# BaseBoard_1.net
KiCad netlist of a schematic drawn in EAGLE
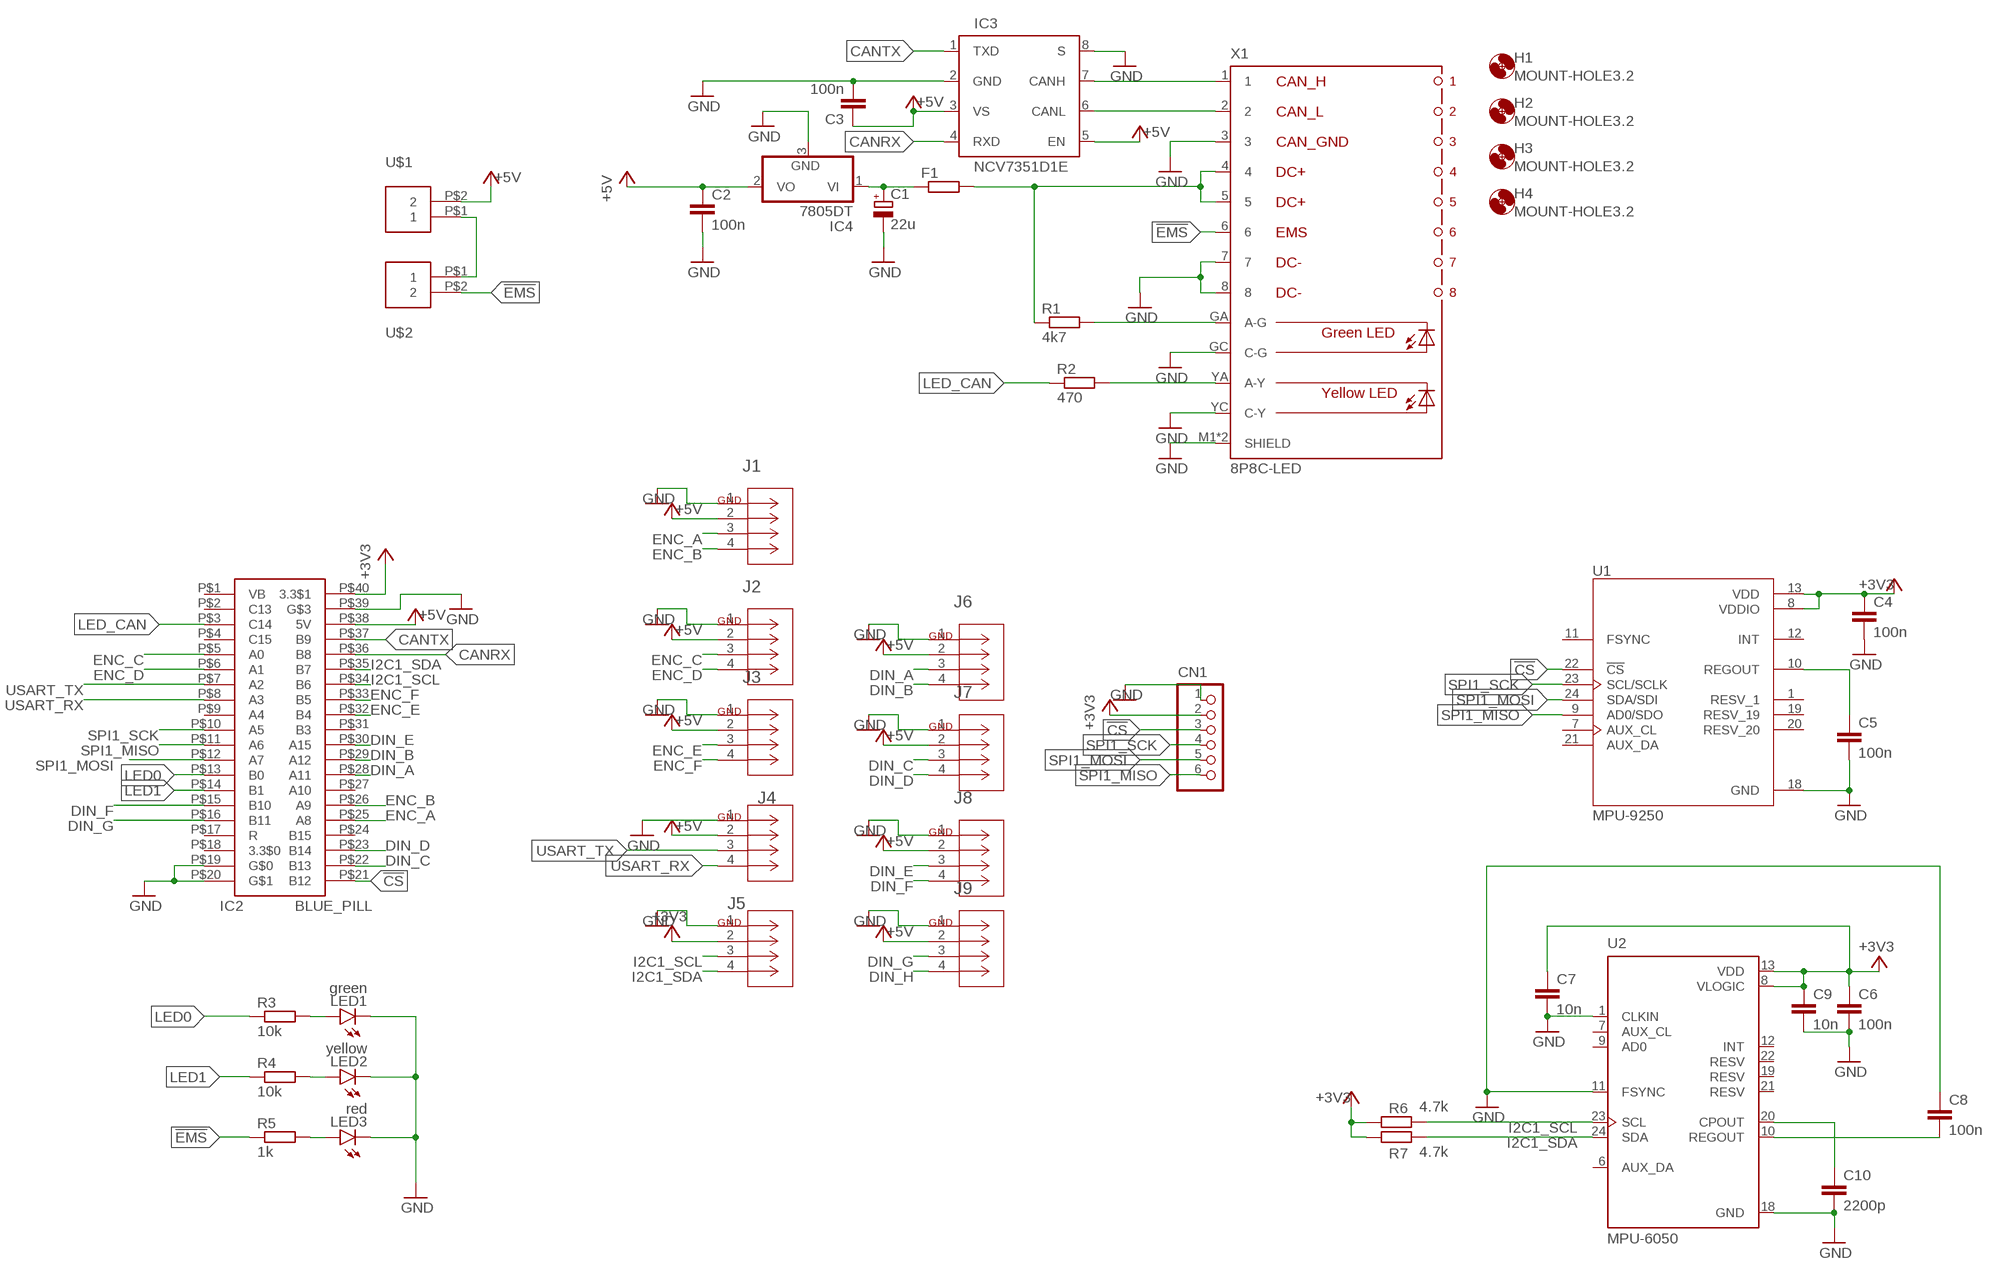
[diagram p0: schematic, sheet 1]

(export (version "E")
  (design (tool "Eeschema 10.0.6"))
  (components
    (comp (ref "C1")
      (value "22u")
      (footprint "eagle-import:E2,5-5")
      (libsource (lib "eagle-import") (part "CPOL-EUE2.5-5"))
    )
    (comp (ref "C2")
      (value "100n")
      (footprint "eagle-import:C0603")
      (libsource (lib "eagle-import") (part "C-EUC0603"))
    )
    (comp (ref "C3")
      (value "100n")
      (footprint "eagle-import:C0603")
      (libsource (lib "eagle-import") (part "C-EUC0603"))
    )
    (comp (ref "C4")
      (value "100n")
      (footprint "eagle-import:C0603")
      (libsource (lib "eagle-import") (part "C-EUC0603"))
    )
    (comp (ref "C5")
      (value "100n")
      (footprint "eagle-import:C0603")
      (libsource (lib "eagle-import") (part "C-EUC0603"))
    )
    (comp (ref "C6")
      (value "100n")
      (footprint "eagle-import:C0603")
      (libsource (lib "eagle-import") (part "C-EUC0603"))
    )
    (comp (ref "C7")
      (value "10n")
      (footprint "eagle-import:C0603")
      (libsource (lib "eagle-import") (part "C-EUC0603"))
    )
    (comp (ref "C8")
      (value "100n")
      (footprint "eagle-import:C0603")
      (libsource (lib "eagle-import") (part "C-EUC0603"))
    )
    (comp (ref "C9")
      (value "10n")
      (footprint "eagle-import:C0603")
      (libsource (lib "eagle-import") (part "C-EUC0603"))
    )
    (comp (ref "C10")
      (value "2200p")
      (footprint "eagle-import:C0603")
      (libsource (lib "eagle-import") (part "C-EUC0603"))
    )
    (comp (ref "CN1")
      (value "S6B-XH-A")
      (footprint "eagle-import:S6B-XH-A")
      (libsource (lib "eagle-import") (part "S6B-XH-A"))
    )
    (comp (ref "F1")
      (value "R-EU_R1206")
      (footprint "eagle-import:R1206")
      (libsource (lib "eagle-import") (part "R-EU_R1206"))
    )
    (comp (ref "H1")
      (value "MOUNT-HOLE3.2")
      (footprint "eagle-import:3,2")
      (libsource (lib "eagle-import") (part "MOUNT-HOLE3.2"))
    )
    (comp (ref "H2")
      (value "MOUNT-HOLE3.2")
      (footprint "eagle-import:3,2")
      (libsource (lib "eagle-import") (part "MOUNT-HOLE3.2"))
    )
    (comp (ref "H3")
      (value "MOUNT-HOLE3.2")
      (footprint "eagle-import:3,2")
      (libsource (lib "eagle-import") (part "MOUNT-HOLE3.2"))
    )
    (comp (ref "H4")
      (value "MOUNT-HOLE3.2")
      (footprint "eagle-import:3,2")
      (libsource (lib "eagle-import") (part "MOUNT-HOLE3.2"))
    )
    (comp (ref "IC2")
      (value "BLUE_PILL")
      (footprint "eagle-import:BLUE_PILL")
      (libsource (lib "eagle-import") (part "BLUE_PILL"))
    )
    (comp (ref "IC3")
      (value "NCV7351D1E")
      (footprint "eagle-import:SO08")
      (libsource (lib "eagle-import") (part "NCV7351D1E"))
    )
    (comp (ref "IC4")
      (value "7805DT")
      (footprint "eagle-import:TO252")
      (libsource (lib "eagle-import") (part "78DT05"))
    )
    (comp (ref "J1")
      (value "EP2.5-4-SIDE")
      (footprint "eagle-import:CONN4_1744426-4")
      (fields (field (name "MANUFACTURER_PART_NUMBER") "17444264"))
      (libsource (lib "eagle-import") (part "EP2.5-4-SIDE"))
    )
    (comp (ref "J2")
      (value "EP2.5-4-SIDE")
      (footprint "eagle-import:CONN4_1744426-4")
      (fields (field (name "MANUFACTURER_PART_NUMBER") "17444264"))
      (libsource (lib "eagle-import") (part "EP2.5-4-SIDE"))
    )
    (comp (ref "J3")
      (value "EP2.5-4-SIDE")
      (footprint "eagle-import:CONN4_1744426-4")
      (fields (field (name "MANUFACTURER_PART_NUMBER") "17444264"))
      (libsource (lib "eagle-import") (part "EP2.5-4-SIDE"))
    )
    (comp (ref "J4")
      (value "EP2.5-4-SIDE")
      (footprint "eagle-import:CONN4_1744426-4")
      (fields (field (name "MANUFACTURER_PART_NUMBER") "17444264"))
      (libsource (lib "eagle-import") (part "EP2.5-4-SIDE"))
    )
    (comp (ref "J5")
      (value "EP2.5-4-SIDE")
      (footprint "eagle-import:CONN4_1744426-4")
      (fields (field (name "MANUFACTURER_PART_NUMBER") "17444264"))
      (libsource (lib "eagle-import") (part "EP2.5-4-SIDE"))
    )
    (comp (ref "J6")
      (value "EP2.5-4-SIDE")
      (footprint "eagle-import:CONN4_1744426-4")
      (fields (field (name "MANUFACTURER_PART_NUMBER") "17444264"))
      (libsource (lib "eagle-import") (part "EP2.5-4-SIDE"))
    )
    (comp (ref "J7")
      (value "EP2.5-4-SIDE")
      (footprint "eagle-import:CONN4_1744426-4")
      (fields (field (name "MANUFACTURER_PART_NUMBER") "17444264"))
      (libsource (lib "eagle-import") (part "EP2.5-4-SIDE"))
    )
    (comp (ref "J8")
      (value "EP2.5-4-SIDE")
      (footprint "eagle-import:CONN4_1744426-4")
      (fields (field (name "MANUFACTURER_PART_NUMBER") "17444264"))
      (libsource (lib "eagle-import") (part "EP2.5-4-SIDE"))
    )
    (comp (ref "J9")
      (value "EP2.5-4-SIDE")
      (footprint "eagle-import:CONN4_1744426-4")
      (fields (field (name "MANUFACTURER_PART_NUMBER") "17444264"))
      (libsource (lib "eagle-import") (part "EP2.5-4-SIDE"))
    )
    (comp (ref "LED1")
      (value "green")
      (footprint "eagle-import:CHIPLED_0805")
      (libsource (lib "eagle-import") (part "LEDCHIPLED_0805"))
    )
    (comp (ref "LED2")
      (value "yellow")
      (footprint "eagle-import:CHIPLED_0805")
      (libsource (lib "eagle-import") (part "LEDCHIPLED_0805"))
    )
    (comp (ref "LED3")
      (value "red")
      (footprint "eagle-import:CHIPLED_0805")
      (libsource (lib "eagle-import") (part "LEDCHIPLED_0805"))
    )
    (comp (ref "R1")
      (value "4k7")
      (footprint "eagle-import:R0603")
      (libsource (lib "eagle-import") (part "R-EU_R0603"))
    )
    (comp (ref "R2")
      (value "470")
      (footprint "eagle-import:R0603")
      (libsource (lib "eagle-import") (part "R-EU_R0603"))
    )
    (comp (ref "R3")
      (value "10k")
      (footprint "eagle-import:R0603")
      (libsource (lib "eagle-import") (part "R-EU_R0603"))
    )
    (comp (ref "R4")
      (value "10k")
      (footprint "eagle-import:R0603")
      (libsource (lib "eagle-import") (part "R-EU_R0603"))
    )
    (comp (ref "R5")
      (value "1k")
      (footprint "eagle-import:R0603")
      (libsource (lib "eagle-import") (part "R-EU_R0603"))
    )
    (comp (ref "R6")
      (value "4.7k")
      (footprint "eagle-import:R0603")
      (libsource (lib "eagle-import") (part "R-EU_R0603"))
    )
    (comp (ref "R7")
      (value "4.7k")
      (footprint "eagle-import:R0603")
      (libsource (lib "eagle-import") (part "R-EU_R0603"))
    )
    (comp (ref "U$1")
      (value "XH-2-STRAIGHT")
      (footprint "eagle-import:CON-XH-2-STRAIGHT")
      (libsource (lib "eagle-import") (part "XH-2-STRAIGHT"))
    )
    (comp (ref "U$2")
      (value "XH-2-STRAIGHT")
      (footprint "eagle-import:CON-XH-2-STRAIGHT")
      (libsource (lib "eagle-import") (part "XH-2-STRAIGHT"))
    )
    (comp (ref "U1")
      (value "MPU-9250")
      (footprint "eagle-import:QFN40P300X300X105-24N")
      (fields (field (name "MF") "TDK InvenSense"))
      (libsource (lib "eagle-import") (part "MPU-9250"))
    )
    (comp (ref "U2")
      (value "MPU-6050")
      (footprint "eagle-import:QFN50P400X400X95-24N")
      (fields (field (name "MF") "TDK InvenSense"))
      (libsource (lib "eagle-import") (part "MPU-6050"))
    )
    (comp (ref "X1")
      (value "8P8C-LED")
      (footprint "eagle-import:8P8C-LED")
      (libsource (lib "eagle-import") (part "8P8C-LED"))
    )
  )
  (nets
    (net (code "1") (name "+3V3") (class "Default")
      (node (ref "C4") (pin "1") (pinfunction "1_1") (pintype "passive"))
      (node (ref "C6") (pin "1") (pinfunction "1_1") (pintype "passive"))
      (node (ref "C7") (pin "1") (pinfunction "1_1") (pintype "passive"))
      (node (ref "C9") (pin "1") (pinfunction "1_1") (pintype "passive"))
      (node (ref "CN1") (pin "2") (pinfunction "2_2") (pintype "passive"))
      (node (ref "IC2") (pin "P$40") (pinfunction "3.3$1_P$40") (pintype "passive"))
      (node (ref "J5") (pin "2") (pinfunction "2_2") (pintype "passive"))
      (node (ref "R6") (pin "1") (pinfunction "1_1") (pintype "passive"))
      (node (ref "R7") (pin "1") (pinfunction "1_1") (pintype "passive"))
      (node (ref "U1") (pin "13") (pinfunction "VDD_13") (pintype "power_in"))
      (node (ref "U1") (pin "8") (pinfunction "VDDIO_8") (pintype "power_in"))
      (node (ref "U2") (pin "13") (pinfunction "VDD_13") (pintype "power_in"))
      (node (ref "U2") (pin "8") (pinfunction "VLOGIC_8") (pintype "power_in"))
    )
    (net (code "2") (name "+5V") (class "Default")
      (node (ref "C2") (pin "1") (pinfunction "1_1") (pintype "passive"))
      (node (ref "C3") (pin "1") (pinfunction "1_1") (pintype "passive"))
      (node (ref "IC2") (pin "P$38") (pinfunction "5V_P$38") (pintype "bidirectional"))
      (node (ref "IC3") (pin "3") (pinfunction "VS_3") (pintype "power_in"))
      (node (ref "IC3") (pin "5") (pinfunction "EN_5") (pintype "input"))
      (node (ref "IC4") (pin "2") (pinfunction "VO_2") (pintype "passive"))
      (node (ref "J1") (pin "2") (pinfunction "2_2") (pintype "passive"))
      (node (ref "J2") (pin "2") (pinfunction "2_2") (pintype "passive"))
      (node (ref "J3") (pin "2") (pinfunction "2_2") (pintype "passive"))
      (node (ref "J4") (pin "2") (pinfunction "2_2") (pintype "passive"))
      (node (ref "J6") (pin "2") (pinfunction "2_2") (pintype "passive"))
      (node (ref "J7") (pin "2") (pinfunction "2_2") (pintype "passive"))
      (node (ref "J8") (pin "2") (pinfunction "2_2") (pintype "passive"))
      (node (ref "J9") (pin "2") (pinfunction "2_2") (pintype "passive"))
      (node (ref "U$1") (pin "P$2") (pinfunction "2_P$2") (pintype "bidirectional"))
    )
    (net (code "3") (name "/DIN_A") (class "Default")
      (node (ref "IC2") (pin "P$28") (pinfunction "A11_P$28") (pintype "bidirectional"))
      (node (ref "J6") (pin "3") (pinfunction "3_3") (pintype "passive"))
    )
    (net (code "4") (name "/DIN_B") (class "Default")
      (node (ref "IC2") (pin "P$29") (pinfunction "A12_P$29") (pintype "bidirectional"))
      (node (ref "J6") (pin "4") (pinfunction "4_4") (pintype "passive"))
    )
    (net (code "5") (name "/DIN_C") (class "Default")
      (node (ref "IC2") (pin "P$22") (pinfunction "B13_P$22") (pintype "bidirectional"))
      (node (ref "J7") (pin "3") (pinfunction "3_3") (pintype "passive"))
    )
    (net (code "6") (name "/DIN_D") (class "Default")
      (node (ref "IC2") (pin "P$23") (pinfunction "B14_P$23") (pintype "bidirectional"))
      (node (ref "J7") (pin "4") (pinfunction "4_4") (pintype "passive"))
    )
    (net (code "7") (name "/DIN_E") (class "Default")
      (node (ref "IC2") (pin "P$30") (pinfunction "A15_P$30") (pintype "bidirectional"))
      (node (ref "J8") (pin "3") (pinfunction "3_3") (pintype "passive"))
    )
    (net (code "8") (name "/DIN_F") (class "Default")
      (node (ref "IC2") (pin "P$15") (pinfunction "B10_P$15") (pintype "bidirectional"))
      (node (ref "J8") (pin "4") (pinfunction "4_4") (pintype "passive"))
    )
    (net (code "9") (name "/DIN_G") (class "Default")
      (node (ref "IC2") (pin "P$16") (pinfunction "B11_P$16") (pintype "bidirectional"))
      (node (ref "J9") (pin "3") (pinfunction "3_3") (pintype "passive"))
    )
    (net (code "10") (name "/DIN_H") (class "Default")
      (node (ref "J9") (pin "4") (pinfunction "4_4") (pintype "passive"))
    )
    (net (code "11") (name "/ENC_A") (class "Default")
      (node (ref "IC2") (pin "P$25") (pinfunction "A8_P$25") (pintype "bidirectional"))
      (node (ref "J1") (pin "3") (pinfunction "3_3") (pintype "passive"))
    )
    (net (code "12") (name "/ENC_B") (class "Default")
      (node (ref "IC2") (pin "P$26") (pinfunction "A9_P$26") (pintype "bidirectional"))
      (node (ref "J1") (pin "4") (pinfunction "4_4") (pintype "passive"))
    )
    (net (code "13") (name "/ENC_C") (class "Default")
      (node (ref "IC2") (pin "P$5") (pinfunction "A0_P$5") (pintype "bidirectional"))
      (node (ref "J2") (pin "3") (pinfunction "3_3") (pintype "passive"))
    )
    (net (code "14") (name "/ENC_D") (class "Default")
      (node (ref "IC2") (pin "P$6") (pinfunction "A1_P$6") (pintype "bidirectional"))
      (node (ref "J2") (pin "4") (pinfunction "4_4") (pintype "passive"))
    )
    (net (code "15") (name "/ENC_E") (class "Default")
      (node (ref "IC2") (pin "P$32") (pinfunction "B4_P$32") (pintype "bidirectional"))
      (node (ref "J3") (pin "3") (pinfunction "3_3") (pintype "passive"))
    )
    (net (code "16") (name "/ENC_F") (class "Default")
      (node (ref "IC2") (pin "P$33") (pinfunction "B5_P$33") (pintype "bidirectional"))
      (node (ref "J3") (pin "4") (pinfunction "4_4") (pintype "passive"))
    )
    (net (code "17") (name "/I2C1_SCL") (class "Default")
      (node (ref "IC2") (pin "P$34") (pinfunction "B6_P$34") (pintype "bidirectional"))
      (node (ref "J5") (pin "3") (pinfunction "3_3") (pintype "passive"))
      (node (ref "R6") (pin "2") (pinfunction "2_2") (pintype "passive"))
      (node (ref "U2") (pin "23") (pinfunction "SCL_23") (pintype "input"))
    )
    (net (code "18") (name "/I2C1_SDA") (class "Default")
      (node (ref "IC2") (pin "P$35") (pinfunction "B7_P$35") (pintype "bidirectional"))
      (node (ref "J5") (pin "4") (pinfunction "4_4") (pintype "passive"))
      (node (ref "R7") (pin "2") (pinfunction "2_2") (pintype "passive"))
      (node (ref "U2") (pin "24") (pinfunction "SDA_24") (pintype "bidirectional"))
    )
    (net (code "19") (name "/~{CS}") (class "Default")
      (node (ref "CN1") (pin "3") (pinfunction "3_3") (pintype "passive"))
      (node (ref "IC2") (pin "P$21") (pinfunction "B12_P$21") (pintype "bidirectional"))
      (node (ref "U1") (pin "22") (pinfunction "~{CS}_22") (pintype "input"))
    )
    (net (code "20") (name "/~{EMS}") (class "Default")
      (node (ref "R5") (pin "1") (pinfunction "1_1") (pintype "passive"))
      (node (ref "U$2") (pin "P$2") (pinfunction "2_P$2") (pintype "bidirectional"))
      (node (ref "X1") (pin "6") (pinfunction "6_6") (pintype "input"))
    )
    (net (code "21") (name "CANRX") (class "Default")
      (node (ref "IC2") (pin "P$36") (pinfunction "B8_P$36") (pintype "bidirectional"))
      (node (ref "IC3") (pin "4") (pinfunction "RXD_4") (pintype "output"))
    )
    (net (code "22") (name "CANTX") (class "Default")
      (node (ref "IC2") (pin "P$37") (pinfunction "B9_P$37") (pintype "bidirectional"))
      (node (ref "IC3") (pin "1") (pinfunction "TXD_1") (pintype "input"))
    )
    (net (code "23") (name "GND") (class "Default")
      (node (ref "C1") (pin "-") (pinfunction "-_-") (pintype "passive"))
      (node (ref "C10") (pin "2") (pinfunction "2_2") (pintype "passive"))
      (node (ref "C2") (pin "2") (pinfunction "2_2") (pintype "passive"))
      (node (ref "C3") (pin "2") (pinfunction "2_2") (pintype "passive"))
      (node (ref "C4") (pin "2") (pinfunction "2_2") (pintype "passive"))
      (node (ref "C5") (pin "2") (pinfunction "2_2") (pintype "passive"))
      (node (ref "C6") (pin "2") (pinfunction "2_2") (pintype "passive"))
      (node (ref "C7") (pin "2") (pinfunction "2_2") (pintype "passive"))
      (node (ref "C8") (pin "1") (pinfunction "1_1") (pintype "passive"))
      (node (ref "C9") (pin "2") (pinfunction "2_2") (pintype "passive"))
      (node (ref "CN1") (pin "1") (pinfunction "1_1") (pintype "passive"))
      (node (ref "IC2") (pin "P$19") (pinfunction "G$0_P$19") (pintype "passive"))
      (node (ref "IC2") (pin "P$20") (pinfunction "G$1_P$20") (pintype "passive"))
      (node (ref "IC2") (pin "P$39") (pinfunction "G$3_P$39") (pintype "passive"))
      (node (ref "IC3") (pin "2") (pinfunction "GND_2") (pintype "power_in"))
      (node (ref "IC3") (pin "8") (pinfunction "S_8") (pintype "input"))
      (node (ref "IC4") (pin "3") (pinfunction "GND_3") (pintype "passive"))
      (node (ref "J1") (pin "1") (pinfunction "1_1") (pintype "passive"))
      (node (ref "J2") (pin "1") (pinfunction "1_1") (pintype "passive"))
      (node (ref "J3") (pin "1") (pinfunction "1_1") (pintype "passive"))
      (node (ref "J4") (pin "1") (pinfunction "1_1") (pintype "passive"))
      (node (ref "J5") (pin "1") (pinfunction "1_1") (pintype "passive"))
      (node (ref "J6") (pin "1") (pinfunction "1_1") (pintype "passive"))
      (node (ref "J7") (pin "1") (pinfunction "1_1") (pintype "passive"))
      (node (ref "J8") (pin "1") (pinfunction "1_1") (pintype "passive"))
      (node (ref "J9") (pin "1") (pinfunction "1_1") (pintype "passive"))
      (node (ref "LED1") (pin "C") (pinfunction "C_C") (pintype "passive"))
      (node (ref "LED2") (pin "C") (pinfunction "C_C") (pintype "passive"))
      (node (ref "LED3") (pin "C") (pinfunction "C_C") (pintype "passive"))
      (node (ref "U1") (pin "18") (pinfunction "GND_18") (pintype "power_in"))
      (node (ref "U2") (pin "1") (pinfunction "CLKIN_1") (pintype "input"))
      (node (ref "U2") (pin "11") (pinfunction "FSYNC_11") (pintype "input"))
      (node (ref "U2") (pin "18") (pinfunction "GND_18") (pintype "power_in"))
      (node (ref "X1") (pin "3") (pinfunction "3_3") (pintype "input"))
      (node (ref "X1") (pin "7") (pinfunction "7_7") (pintype "input"))
      (node (ref "X1") (pin "8") (pinfunction "8_8") (pintype "input"))
      (node (ref "X1") (pin "GC") (pinfunction "C-G_GC") (pintype "passive"))
      (node (ref "X1") (pin "M1") (pinfunction "SHIELD_M1") (pintype "passive"))
      (node (ref "X1") (pin "M2") (pinfunction "SHIELD_M2") (pintype "passive"))
      (node (ref "X1") (pin "YC") (pinfunction "C-Y_YC") (pintype "passive"))
    )
    (net (code "24") (name "LED0") (class "Default")
      (node (ref "IC2") (pin "P$13") (pinfunction "B0_P$13") (pintype "bidirectional"))
      (node (ref "R3") (pin "1") (pinfunction "1_1") (pintype "passive"))
    )
    (net (code "25") (name "LED1") (class "Default")
      (node (ref "IC2") (pin "P$14") (pinfunction "B1_P$14") (pintype "bidirectional"))
      (node (ref "R4") (pin "1") (pinfunction "1_1") (pintype "passive"))
    )
    (net (code "26") (name "LED_CAN") (class "Default")
      (node (ref "IC2") (pin "P$3") (pinfunction "C14_P$3") (pintype "bidirectional"))
      (node (ref "R2") (pin "1") (pinfunction "1_1") (pintype "passive"))
    )
    (net (code "27") (name "Net-(F1-Pad2)") (class "Default")
      (node (ref "F1") (pin "2") (pinfunction "2_2") (pintype "passive"))
      (node (ref "R1") (pin "1") (pinfunction "1_1") (pintype "passive"))
      (node (ref "X1") (pin "4") (pinfunction "4_4") (pintype "input"))
      (node (ref "X1") (pin "5") (pinfunction "5_5") (pintype "input"))
    )
    (net (code "28") (name "Net-(IC3-CANH)") (class "Default")
      (node (ref "IC3") (pin "7") (pinfunction "CANH_7") (pintype "output"))
      (node (ref "X1") (pin "1") (pinfunction "1_1") (pintype "input"))
    )
    (net (code "29") (name "Net-(IC3-CANL)") (class "Default")
      (node (ref "IC3") (pin "6") (pinfunction "CANL_6") (pintype "output"))
      (node (ref "X1") (pin "2") (pinfunction "2_2") (pintype "input"))
    )
    (net (code "30") (name "Net-(IC4-VI)") (class "Default")
      (node (ref "C1") (pin "+") (pinfunction "+_+") (pintype "passive"))
      (node (ref "F1") (pin "1") (pinfunction "1_1") (pintype "passive"))
      (node (ref "IC4") (pin "1") (pinfunction "VI_1") (pintype "input"))
    )
    (net (code "31") (name "Net-(LED1-PadA)") (class "Default")
      (node (ref "LED1") (pin "A") (pinfunction "A_A") (pintype "passive"))
      (node (ref "R3") (pin "2") (pinfunction "2_2") (pintype "passive"))
    )
    (net (code "32") (name "Net-(LED2-PadA)") (class "Default")
      (node (ref "LED2") (pin "A") (pinfunction "A_A") (pintype "passive"))
      (node (ref "R4") (pin "2") (pinfunction "2_2") (pintype "passive"))
    )
    (net (code "33") (name "Net-(LED3-PadA)") (class "Default")
      (node (ref "LED3") (pin "A") (pinfunction "A_A") (pintype "passive"))
      (node (ref "R5") (pin "2") (pinfunction "2_2") (pintype "passive"))
    )
    (net (code "34") (name "Net-(U$1-1)") (class "Default")
      (node (ref "U$1") (pin "P$1") (pinfunction "1_P$1") (pintype "bidirectional"))
      (node (ref "U$2") (pin "P$1") (pinfunction "1_P$1") (pintype "bidirectional"))
    )
    (net (code "35") (name "Net-(U1-REGOUT)") (class "Default")
      (node (ref "C5") (pin "1") (pinfunction "1_1") (pintype "passive"))
      (node (ref "U1") (pin "10") (pinfunction "REGOUT_10") (pintype "output"))
    )
    (net (code "36") (name "Net-(U2-CPOUT)") (class "Default")
      (node (ref "C10") (pin "1") (pinfunction "1_1") (pintype "passive"))
      (node (ref "U2") (pin "20") (pinfunction "CPOUT_20") (pintype "passive"))
    )
    (net (code "37") (name "Net-(U2-REGOUT)") (class "Default")
      (node (ref "C8") (pin "2") (pinfunction "2_2") (pintype "passive"))
      (node (ref "U2") (pin "10") (pinfunction "REGOUT_10") (pintype "passive"))
    )
    (net (code "38") (name "Net-(X1-A-G)") (class "Default")
      (node (ref "R1") (pin "2") (pinfunction "2_2") (pintype "passive"))
      (node (ref "X1") (pin "GA") (pinfunction "A-G_GA") (pintype "passive"))
    )
    (net (code "39") (name "Net-(X1-A-Y)") (class "Default")
      (node (ref "R2") (pin "2") (pinfunction "2_2") (pintype "passive"))
      (node (ref "X1") (pin "YA") (pinfunction "A-Y_YA") (pintype "passive"))
    )
    (net (code "40") (name "SPI1_MISO") (class "Default")
      (node (ref "CN1") (pin "6") (pinfunction "6_6") (pintype "passive"))
      (node (ref "IC2") (pin "P$11") (pinfunction "A6_P$11") (pintype "bidirectional"))
      (node (ref "U1") (pin "9") (pinfunction "AD0/SDO_9") (pintype "output"))
    )
    (net (code "41") (name "SPI1_MOSI") (class "Default")
      (node (ref "CN1") (pin "5") (pinfunction "5_5") (pintype "passive"))
      (node (ref "IC2") (pin "P$12") (pinfunction "A7_P$12") (pintype "bidirectional"))
      (node (ref "U1") (pin "24") (pinfunction "SDA/SDI_24") (pintype "bidirectional"))
    )
    (net (code "42") (name "SPI1_SCK") (class "Default")
      (node (ref "CN1") (pin "4") (pinfunction "4_4") (pintype "passive"))
      (node (ref "IC2") (pin "P$10") (pinfunction "A5_P$10") (pintype "bidirectional"))
      (node (ref "U1") (pin "23") (pinfunction "SCL/SCLK_23") (pintype "input"))
    )
    (net (code "43") (name "USART_RX") (class "Default")
      (node (ref "IC2") (pin "P$8") (pinfunction "A3_P$8") (pintype "bidirectional"))
      (node (ref "J4") (pin "4") (pinfunction "4_4") (pintype "passive"))
    )
    (net (code "44") (name "USART_TX") (class "Default")
      (node (ref "IC2") (pin "P$7") (pinfunction "A2_P$7") (pintype "bidirectional"))
      (node (ref "J4") (pin "3") (pinfunction "3_3") (pintype "passive"))
    )
    (net (code "45") (name "unconnected-(IC2-3.3$0-PadP$18)") (class "Default")
      (node (ref "IC2") (pin "P$18") (pinfunction "3.3$0_P$18") (pintype "passive"))
    )
    (net (code "46") (name "unconnected-(IC2-A4-PadP$9)") (class "Default")
      (node (ref "IC2") (pin "P$9") (pinfunction "A4_P$9") (pintype "bidirectional"))
    )
    (net (code "47") (name "unconnected-(IC2-A10-PadP$27)") (class "Default")
      (node (ref "IC2") (pin "P$27") (pinfunction "A10_P$27") (pintype "bidirectional"))
    )
    (net (code "48") (name "unconnected-(IC2-B3-PadP$31)") (class "Default")
      (node (ref "IC2") (pin "P$31") (pinfunction "B3_P$31") (pintype "bidirectional"))
    )
    (net (code "49") (name "unconnected-(IC2-B15-PadP$24)") (class "Default")
      (node (ref "IC2") (pin "P$24") (pinfunction "B15_P$24") (pintype "bidirectional"))
    )
    (net (code "50") (name "unconnected-(IC2-C13-PadP$2)") (class "Default")
      (node (ref "IC2") (pin "P$2") (pinfunction "C13_P$2") (pintype "bidirectional"))
    )
    (net (code "51") (name "unconnected-(IC2-C15-PadP$4)") (class "Default")
      (node (ref "IC2") (pin "P$4") (pinfunction "C15_P$4") (pintype "bidirectional"))
    )
    (net (code "52") (name "unconnected-(IC2-R-PadP$17)") (class "Default")
      (node (ref "IC2") (pin "P$17") (pinfunction "R_P$17") (pintype "bidirectional"))
    )
    (net (code "53") (name "unconnected-(IC2-VB-PadP$1)") (class "Default")
      (node (ref "IC2") (pin "P$1") (pinfunction "VB_P$1") (pintype "bidirectional"))
    )
    (net (code "54") (name "unconnected-(U1-AUX_CL-Pad7)") (class "Default")
      (node (ref "U1") (pin "7") (pinfunction "AUX_CL_7") (pintype "input"))
    )
    (net (code "55") (name "unconnected-(U1-AUX_DA-Pad21)") (class "Default")
      (node (ref "U1") (pin "21") (pinfunction "AUX_DA_21") (pintype "input"))
    )
    (net (code "56") (name "unconnected-(U1-FSYNC-Pad11)") (class "Default")
      (node (ref "U1") (pin "11") (pinfunction "FSYNC_11") (pintype "input"))
    )
    (net (code "57") (name "unconnected-(U1-INT-Pad12)") (class "Default")
      (node (ref "U1") (pin "12") (pinfunction "INT_12") (pintype "output"))
    )
    (net (code "58") (name "unconnected-(U1-RESV_1-Pad1)") (class "Default")
      (node (ref "U1") (pin "1") (pinfunction "RESV_1_1") (pintype "passive"))
    )
    (net (code "59") (name "unconnected-(U1-RESV_19-Pad19)") (class "Default")
      (node (ref "U1") (pin "19") (pinfunction "RESV_19_19") (pintype "passive"))
    )
    (net (code "60") (name "unconnected-(U1-RESV_20-Pad20)") (class "Default")
      (node (ref "U1") (pin "20") (pinfunction "RESV_20_20") (pintype "passive"))
    )
    (net (code "61") (name "unconnected-(U2-AD0-Pad9)") (class "Default")
      (node (ref "U2") (pin "9") (pinfunction "AD0_9") (pintype "input"))
    )
    (net (code "62") (name "unconnected-(U2-AUX_CL-Pad7)") (class "Default")
      (node (ref "U2") (pin "7") (pinfunction "AUX_CL_7") (pintype "input"))
    )
    (net (code "63") (name "unconnected-(U2-AUX_DA-Pad6)") (class "Default")
      (node (ref "U2") (pin "6") (pinfunction "AUX_DA_6") (pintype "bidirectional"))
    )
    (net (code "64") (name "unconnected-(U2-INT-Pad12)") (class "Default")
      (node (ref "U2") (pin "12") (pinfunction "INT_12") (pintype "output"))
    )
    (net (code "65") (name "unconnected-(U2-RESV-Pad19)") (class "Default")
      (node (ref "U2") (pin "19") (pinfunction "RESV_19") (pintype "passive"))
    )
    (net (code "66") (name "unconnected-(U2-RESV-Pad21)") (class "Default")
      (node (ref "U2") (pin "21") (pinfunction "RESV_21") (pintype "passive"))
    )
    (net (code "67") (name "unconnected-(U2-RESV-Pad22)") (class "Default")
      (node (ref "U2") (pin "22") (pinfunction "RESV_22") (pintype "passive"))
    )
  )
)
